# 27_BoardPowerSupply_1.net
KiCad netlist of a schematic drawn in Altium Designer
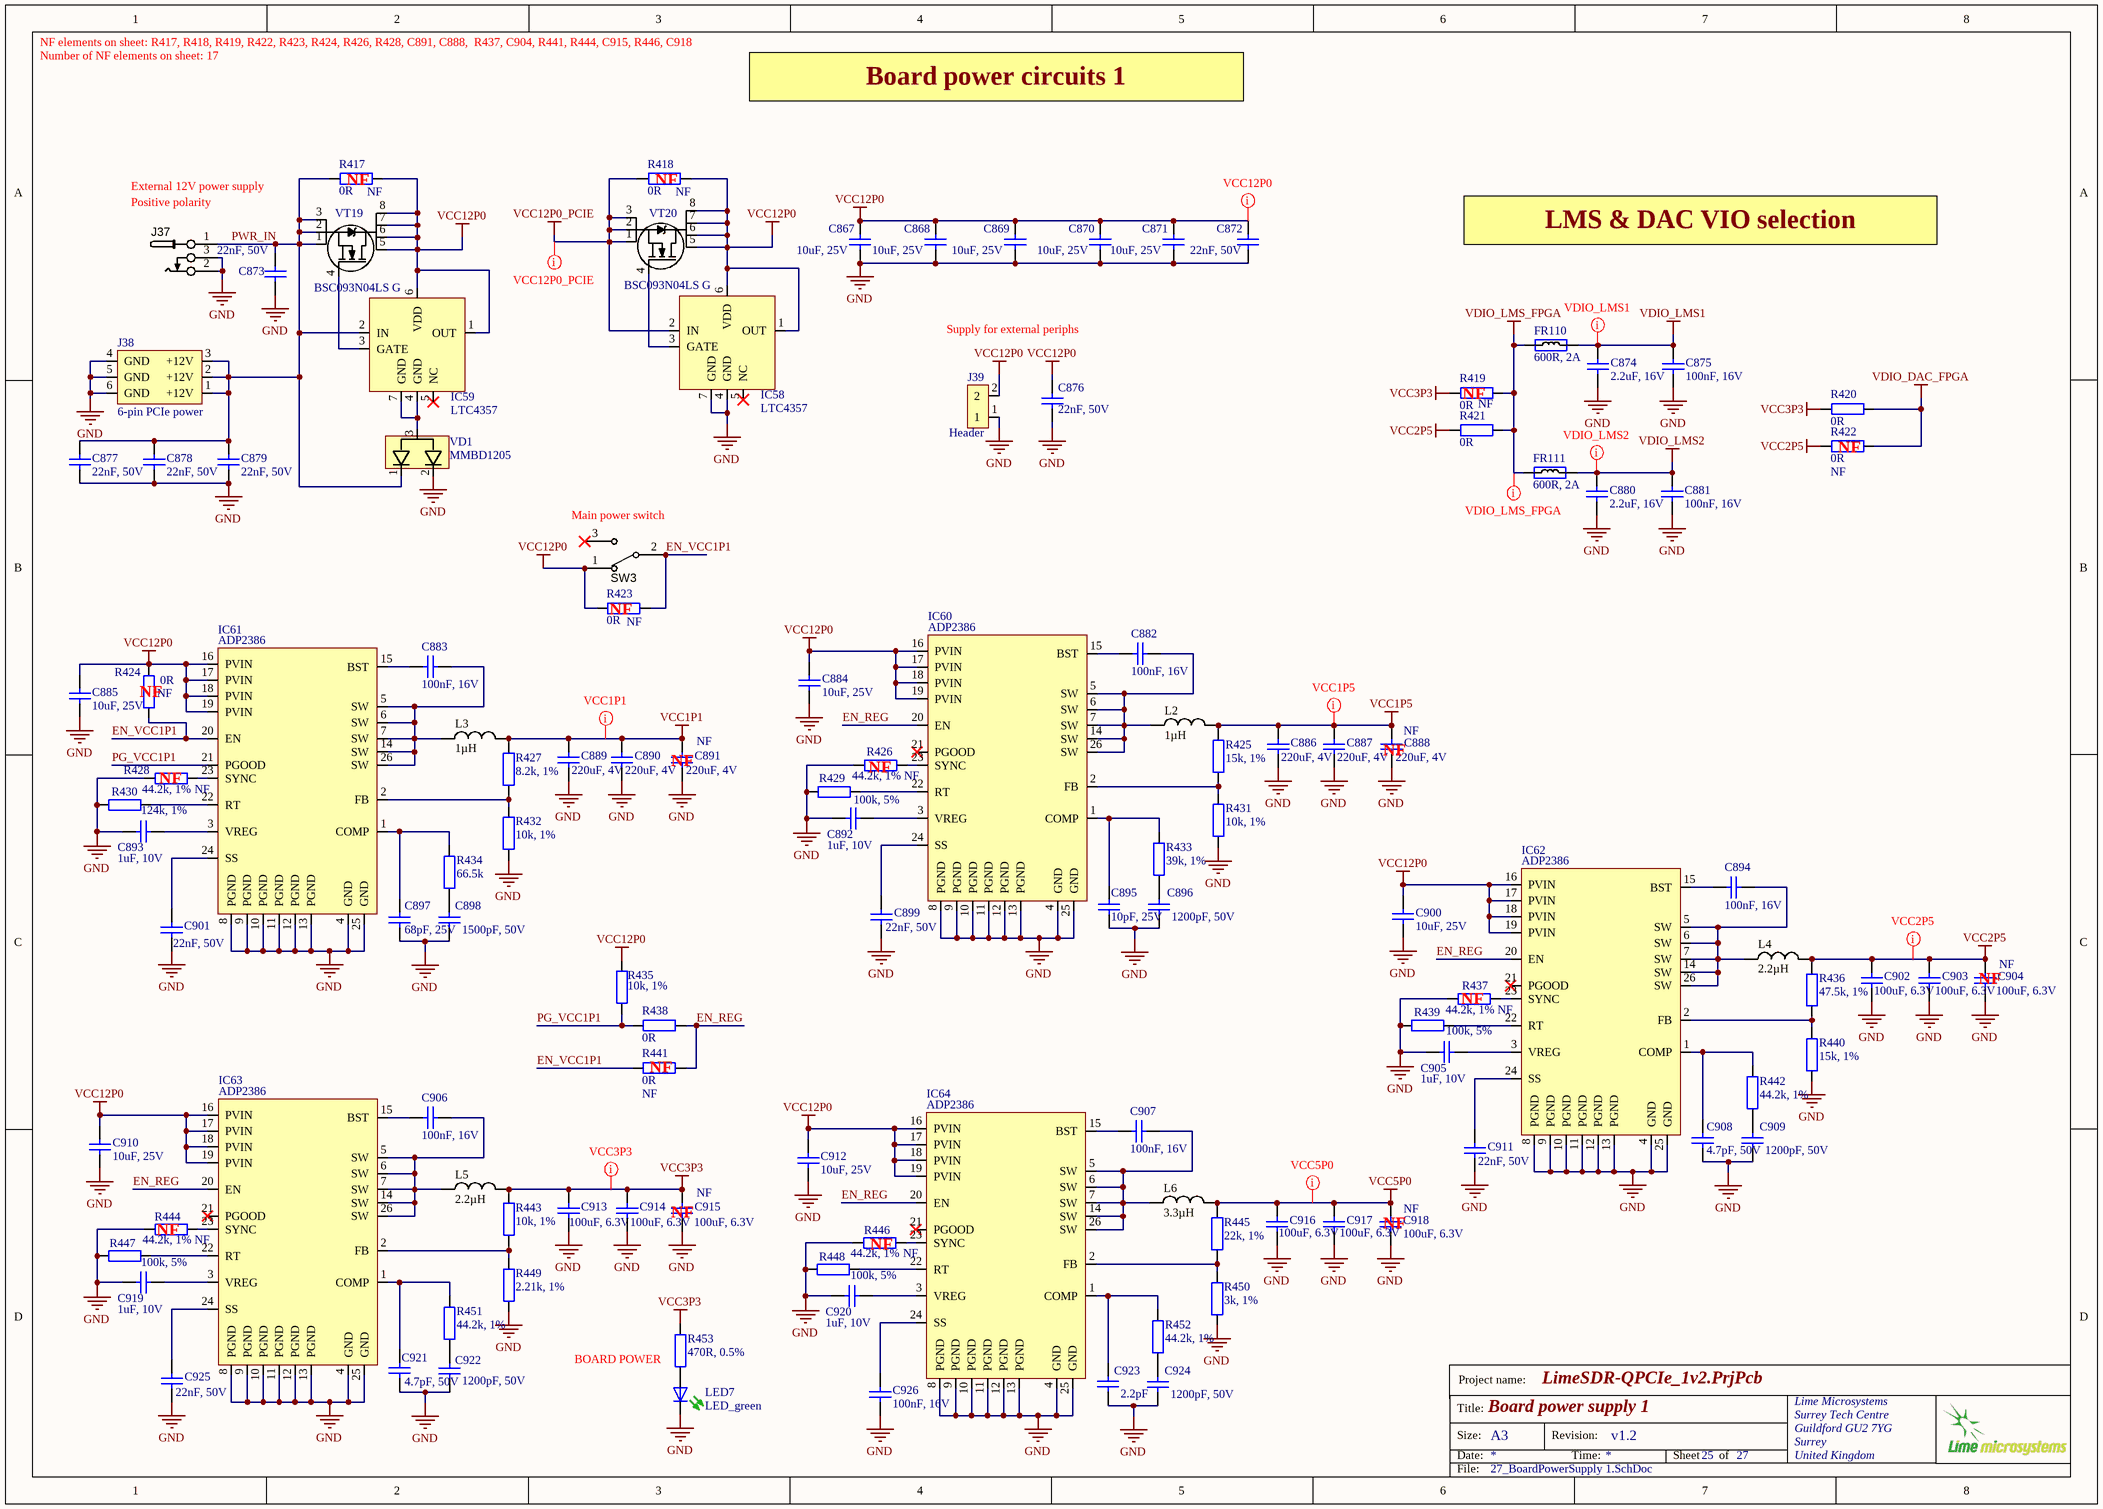
[diagram p0: 27_BoardPowerSupply 1.SchDoc]

(export (version "E")
  (design (tool "Eeschema 10.0.6"))
  (components
    (comp (ref "C867")
      (value "10uF, 25V")
      (footprint "CAP0603")
      (fields
        (field (name "MANUFACTURER") "Murata Electronics North America")
        (field (name "TOLERANCE") "±20%")
      )
      (libsource (lib "LimeMicroAltiumLib_schLib") (part "Cap_0603"))
    )
    (comp (ref "C868")
      (value "10uF, 25V")
      (footprint "CAP0603")
      (fields
        (field (name "MANUFACTURER") "Murata Electronics North America")
        (field (name "TOLERANCE") "±20%")
      )
      (libsource (lib "LimeMicroAltiumLib_schLib") (part "Cap_0603"))
    )
    (comp (ref "C869")
      (value "10uF, 25V")
      (footprint "CAP0603")
      (fields
        (field (name "MANUFACTURER") "Murata Electronics North America")
        (field (name "TOLERANCE") "±20%")
      )
      (libsource (lib "LimeMicroAltiumLib_schLib") (part "Cap_0603"))
    )
    (comp (ref "C870")
      (value "10uF, 25V")
      (footprint "CAP0603")
      (fields
        (field (name "MANUFACTURER") "Murata Electronics North America")
        (field (name "TOLERANCE") "±20%")
      )
      (libsource (lib "LimeMicroAltiumLib_schLib") (part "Cap_0603"))
    )
    (comp (ref "C871")
      (value "10uF, 25V")
      (footprint "CAP0603")
      (fields
        (field (name "MANUFACTURER") "Murata Electronics North America")
        (field (name "TOLERANCE") "±20%")
      )
      (libsource (lib "LimeMicroAltiumLib_schLib") (part "Cap_0603"))
    )
    (comp (ref "C872")
      (value "22nF, 50V")
      (footprint "CAP0402")
      (fields (field (name "TOLERANCE") "±10%") (field (name "MANUFACTURER") "Kemet"))
      (libsource (lib "LimeMicroAltiumLib_schLib") (part "Cap_0402"))
    )
    (comp (ref "C873")
      (value "22nF, 50V")
      (footprint "CAP0402")
      (fields (field (name "TOLERANCE") "±10%") (field (name "MANUFACTURER") "Kemet"))
      (libsource (lib "LimeMicroAltiumLib_schLib") (part "Cap_0402"))
    )
    (comp (ref "C874")
      (value "2.2uF, 16V")
      (footprint "CAP0402")
      (description "CAP CER 2.2UF 16V 10% X5R 0402")
      (fields (field (name "MANUFACTURER") "TDK Corporation") (field (name "TOLERANCE") "±20%"))
      (libsource (lib "LimeMicroAltiumLib_schLib") (part "Cap_0402"))
    )
    (comp (ref "C875")
      (value "100nF, 16V")
      (footprint "CAP0402")
      (fields
        (field (name "MANUFACTURER") "Murata Electronics")
        (field (name "TOLERANCE") "10 %")
        (field (name "MANUFACTURER PART NUMBER") "GRM155R71C104KA88D")
      )
      (libsource (lib "LimeMicroAltiumLib_schLib") (part "Cap_0402"))
    )
    (comp (ref "C876")
      (value "22nF, 50V")
      (footprint "CAP0402")
      (fields (field (name "TOLERANCE") "±10%") (field (name "MANUFACTURER") "Kemet"))
      (libsource (lib "LimeMicroAltiumLib_schLib") (part "Cap_0402"))
    )
    (comp (ref "C877")
      (value "22nF, 50V")
      (footprint "CAP0402")
      (fields (field (name "TOLERANCE") "±10%") (field (name "MANUFACTURER") "Kemet"))
      (libsource (lib "LimeMicroAltiumLib_schLib") (part "Cap_0402"))
    )
    (comp (ref "C878")
      (value "22nF, 50V")
      (footprint "CAP0402")
      (fields (field (name "TOLERANCE") "±10%") (field (name "MANUFACTURER") "Kemet"))
      (libsource (lib "LimeMicroAltiumLib_schLib") (part "Cap_0402"))
    )
    (comp (ref "C879")
      (value "22nF, 50V")
      (footprint "CAP0402")
      (fields (field (name "TOLERANCE") "±10%") (field (name "MANUFACTURER") "Kemet"))
      (libsource (lib "LimeMicroAltiumLib_schLib") (part "Cap_0402"))
    )
    (comp (ref "C880")
      (value "2.2uF, 16V")
      (footprint "CAP0402")
      (description "CAP CER 2.2UF 16V 10% X5R 0402")
      (fields (field (name "MANUFACTURER") "TDK Corporation") (field (name "TOLERANCE") "±20%"))
      (libsource (lib "LimeMicroAltiumLib_schLib") (part "Cap_0402"))
    )
    (comp (ref "C881")
      (value "100nF, 16V")
      (footprint "CAP0402")
      (fields
        (field (name "MANUFACTURER") "Murata Electronics")
        (field (name "TOLERANCE") "10 %")
        (field (name "MANUFACTURER PART NUMBER") "GRM155R71C104KA88D")
      )
      (libsource (lib "LimeMicroAltiumLib_schLib") (part "Cap_0402"))
    )
    (comp (ref "C882")
      (value "100nF, 16V")
      (footprint "CAP0402")
      (fields
        (field (name "MANUFACTURER") "Murata Electronics")
        (field (name "TOLERANCE") "10 %")
        (field (name "MANUFACTURER PART NUMBER") "GRM155R71C104KA88D")
      )
      (libsource (lib "LimeMicroAltiumLib_schLib") (part "Cap_0402"))
    )
    (comp (ref "C883")
      (value "100nF, 16V")
      (footprint "CAP0402")
      (fields
        (field (name "MANUFACTURER") "Murata Electronics")
        (field (name "TOLERANCE") "10 %")
        (field (name "MANUFACTURER PART NUMBER") "GRM155R71C104KA88D")
      )
      (libsource (lib "LimeMicroAltiumLib_schLib") (part "Cap_0402"))
    )
    (comp (ref "C884")
      (value "10uF, 25V")
      (footprint "CAP0805")
      (fields
        (field (name "MANUFACTURER") "Murata Electronics North America")
        (field (name "TOLERANCE") "±10%")
      )
      (libsource (lib "LimeMicroAltiumLib_schLib") (part "Cap_0805"))
    )
    (comp (ref "C885")
      (value "10uF, 25V")
      (footprint "CAP0805")
      (fields
        (field (name "MANUFACTURER") "Murata Electronics North America")
        (field (name "TOLERANCE") "±10%")
      )
      (libsource (lib "LimeMicroAltiumLib_schLib") (part "Cap_0805"))
    )
    (comp (ref "C886")
      (value "220uF, 4V")
      (footprint "CAP1206")
      (fields
        (field (name "MANUFACTURER PART NUMBER") "GRM31CR60G227ME11L")
        (field (name "MANUFACTURER") "Murata Electronics North America")
        (field (name "TOLERANCE") "±20%")
      )
      (libsource (lib "LimeFPGAboard_schLib") (part "Cap_1206"))
    )
    (comp (ref "C887")
      (value "220uF, 4V")
      (footprint "CAP1206")
      (fields
        (field (name "MANUFACTURER PART NUMBER") "GRM31CR60G227ME11L")
        (field (name "MANUFACTURER") "Murata Electronics North America")
        (field (name "TOLERANCE") "±20%")
      )
      (libsource (lib "LimeFPGAboard_schLib") (part "Cap_1206"))
    )
    (comp (ref "C888")
      (value "220uF, 4V")
      (footprint "CAP1206")
      (fields
        (field (name "MANUFACTURER PART NUMBER") "GRM31CR60G227ME11L")
        (field (name "MANUFACTURER") "Murata Electronics North America")
        (field (name "TOLERANCE") "±20%")
        (field (name "ASSEMBLY INFO") "NF")
      )
      (libsource (lib "LimeFPGAboard_schLib") (part "Cap_1206"))
    )
    (comp (ref "C889")
      (value "220uF, 4V")
      (footprint "CAP1206")
      (fields
        (field (name "MANUFACTURER PART NUMBER") "GRM31CR60G227ME11L")
        (field (name "MANUFACTURER") "Murata Electronics North America")
        (field (name "TOLERANCE") "±20%")
      )
      (libsource (lib "LimeFPGAboard_schLib") (part "Cap_1206"))
    )
    (comp (ref "C890")
      (value "220uF, 4V")
      (footprint "CAP1206")
      (fields
        (field (name "MANUFACTURER PART NUMBER") "GRM31CR60G227ME11L")
        (field (name "MANUFACTURER") "Murata Electronics North America")
        (field (name "TOLERANCE") "±20%")
      )
      (libsource (lib "LimeFPGAboard_schLib") (part "Cap_1206"))
    )
    (comp (ref "C891")
      (value "220uF, 4V")
      (footprint "CAP1206")
      (fields
        (field (name "MANUFACTURER PART NUMBER") "GRM31CR60G227ME11L")
        (field (name "MANUFACTURER") "Murata Electronics North America")
        (field (name "TOLERANCE") "±20%")
        (field (name "ASSEMBLY INFO") "NF")
      )
      (libsource (lib "LimeFPGAboard_schLib") (part "Cap_1206"))
    )
    (comp (ref "C892")
      (value "1uF, 10V")
      (footprint "CAP0402")
      (fields (field (name "MANUFACTURER") "TDK"))
      (libsource (lib "LimeMicroAltiumLib_schLib") (part "Cap_0402"))
    )
    (comp (ref "C893")
      (value "1uF, 10V")
      (footprint "CAP0402")
      (fields (field (name "MANUFACTURER") "TDK"))
      (libsource (lib "LimeMicroAltiumLib_schLib") (part "Cap_0402"))
    )
    (comp (ref "C894")
      (value "100nF, 16V")
      (footprint "CAP0402")
      (fields
        (field (name "MANUFACTURER") "Murata Electronics")
        (field (name "TOLERANCE") "10 %")
        (field (name "MANUFACTURER PART NUMBER") "GRM155R71C104KA88D")
      )
      (libsource (lib "LimeMicroAltiumLib_schLib") (part "Cap_0402"))
    )
    (comp (ref "C895")
      (value "10pF, 25V")
      (footprint "CAP0402")
      (fields (field (name "MANUFACTURER") "AVX"))
      (libsource (lib "LimeMicroAltiumLib_schLib") (part "Cap_0402"))
    )
    (comp (ref "C896")
      (value "1200pF, 50V")
      (footprint "CAP0402")
      (fields (field (name "MANUFACTURER") "Kemet") (field (name "TOLERANCE") "±5%"))
      (libsource (lib "LimeMicroAltiumLib_schLib") (part "Cap_0402"))
    )
    (comp (ref "C897")
      (value "68pF, 25V")
      (footprint "CAP0402")
      (fields (field (name "TOLERANCE") "±1%") (field (name "MANUFACTURER") "Kemet"))
      (libsource (lib "LimeMicroAltiumLib_schLib") (part "Cap_0402"))
    )
    (comp (ref "C898")
      (value "1500pF, 50V")
      (footprint "CAP0402")
      (fields
        (field (name "MANUFACTURER") "Samsung Electro-Mechanics America, Inc.")
        (field (name "TOLERANCE") "±10%")
      )
      (libsource (lib "LimeMicroAltiumLib_schLib") (part "Cap_0402"))
    )
    (comp (ref "C899")
      (value "22nF, 50V")
      (footprint "CAP0402")
      (fields (field (name "TOLERANCE") "±10%") (field (name "MANUFACTURER") "Kemet"))
      (libsource (lib "LimeMicroAltiumLib_schLib") (part "Cap_0402"))
    )
    (comp (ref "C900")
      (value "10uF, 25V")
      (footprint "CAP0805")
      (fields
        (field (name "MANUFACTURER") "Murata Electronics North America")
        (field (name "TOLERANCE") "±10%")
      )
      (libsource (lib "LimeMicroAltiumLib_schLib") (part "Cap_0805"))
    )
    (comp (ref "C901")
      (value "22nF, 50V")
      (footprint "CAP0402")
      (fields (field (name "TOLERANCE") "±10%") (field (name "MANUFACTURER") "Kemet"))
      (libsource (lib "LimeMicroAltiumLib_schLib") (part "Cap_0402"))
    )
    (comp (ref "C902")
      (value "100uF, 6.3V")
      (footprint "CAP1206")
      (fields (field (name "MANUFACTURER") "MURATA"))
      (libsource (lib "LimeFPGAboard_schLib") (part "Cap_1206"))
    )
    (comp (ref "C903")
      (value "100uF, 6.3V")
      (footprint "CAP1206")
      (fields (field (name "MANUFACTURER") "MURATA"))
      (libsource (lib "LimeFPGAboard_schLib") (part "Cap_1206"))
    )
    (comp (ref "C904")
      (value "100uF, 6.3V")
      (footprint "CAP1206")
      (fields (field (name "MANUFACTURER") "MURATA") (field (name "ASSEMBLY INFO") "NF"))
      (libsource (lib "LimeFPGAboard_schLib") (part "Cap_1206"))
    )
    (comp (ref "C905")
      (value "1uF, 10V")
      (footprint "CAP0402")
      (fields (field (name "MANUFACTURER") "TDK"))
      (libsource (lib "LimeMicroAltiumLib_schLib") (part "Cap_0402"))
    )
    (comp (ref "C906")
      (value "100nF, 16V")
      (footprint "CAP0402")
      (fields
        (field (name "MANUFACTURER") "Murata Electronics")
        (field (name "TOLERANCE") "10 %")
        (field (name "MANUFACTURER PART NUMBER") "GRM155R71C104KA88D")
      )
      (libsource (lib "LimeMicroAltiumLib_schLib") (part "Cap_0402"))
    )
    (comp (ref "C907")
      (value "100nF, 16V")
      (footprint "CAP0402")
      (fields
        (field (name "MANUFACTURER") "Murata Electronics")
        (field (name "TOLERANCE") "10 %")
        (field (name "MANUFACTURER PART NUMBER") "GRM155R71C104KA88D")
      )
      (libsource (lib "LimeMicroAltiumLib_schLib") (part "Cap_0402"))
    )
    (comp (ref "C908")
      (value "4.7pF, 50V")
      (footprint "CAP0402")
      (fields (field (name "MANUFACTURER") "MURATA"))
      (libsource (lib "LimeMicroAltiumLib_schLib") (part "Cap_0402"))
    )
    (comp (ref "C909")
      (value "1200pF, 50V")
      (footprint "CAP0402")
      (fields (field (name "MANUFACTURER") "Kemet") (field (name "TOLERANCE") "±5%"))
      (libsource (lib "LimeMicroAltiumLib_schLib") (part "Cap_0402"))
    )
    (comp (ref "C910")
      (value "10uF, 25V")
      (footprint "CAP0805")
      (fields
        (field (name "MANUFACTURER") "Murata Electronics North America")
        (field (name "TOLERANCE") "±10%")
      )
      (libsource (lib "LimeMicroAltiumLib_schLib") (part "Cap_0805"))
    )
    (comp (ref "C911")
      (value "22nF, 50V")
      (footprint "CAP0402")
      (fields (field (name "TOLERANCE") "±10%") (field (name "MANUFACTURER") "Kemet"))
      (libsource (lib "LimeMicroAltiumLib_schLib") (part "Cap_0402"))
    )
    (comp (ref "C912")
      (value "10uF, 25V")
      (footprint "CAP0805")
      (fields
        (field (name "MANUFACTURER") "Murata Electronics North America")
        (field (name "TOLERANCE") "±10%")
      )
      (libsource (lib "LimeMicroAltiumLib_schLib") (part "Cap_0805"))
    )
    (comp (ref "C913")
      (value "100uF, 6.3V")
      (footprint "CAP1206")
      (fields (field (name "MANUFACTURER") "MURATA"))
      (libsource (lib "LimeFPGAboard_schLib") (part "Cap_1206"))
    )
    (comp (ref "C914")
      (value "100uF, 6.3V")
      (footprint "CAP1206")
      (fields (field (name "MANUFACTURER") "MURATA"))
      (libsource (lib "LimeFPGAboard_schLib") (part "Cap_1206"))
    )
    (comp (ref "C915")
      (value "100uF, 6.3V")
      (footprint "CAP1206")
      (fields (field (name "MANUFACTURER") "MURATA") (field (name "ASSEMBLY INFO") "NF"))
      (libsource (lib "LimeFPGAboard_schLib") (part "Cap_1206"))
    )
    (comp (ref "C916")
      (value "100uF, 6.3V")
      (footprint "CAP1206")
      (fields (field (name "MANUFACTURER") "MURATA"))
      (libsource (lib "LimeFPGAboard_schLib") (part "Cap_1206"))
    )
    (comp (ref "C917")
      (value "100uF, 6.3V")
      (footprint "CAP1206")
      (fields (field (name "MANUFACTURER") "MURATA"))
      (libsource (lib "LimeFPGAboard_schLib") (part "Cap_1206"))
    )
    (comp (ref "C918")
      (value "100uF, 6.3V")
      (footprint "CAP1206")
      (fields (field (name "MANUFACTURER") "MURATA") (field (name "ASSEMBLY INFO") "NF"))
      (libsource (lib "LimeFPGAboard_schLib") (part "Cap_1206"))
    )
    (comp (ref "C919")
      (value "1uF, 10V")
      (footprint "CAP0402")
      (fields (field (name "MANUFACTURER") "TDK"))
      (libsource (lib "LimeMicroAltiumLib_schLib") (part "Cap_0402"))
    )
    (comp (ref "C920")
      (value "1uF, 10V")
      (footprint "CAP0402")
      (fields (field (name "MANUFACTURER") "TDK"))
      (libsource (lib "LimeMicroAltiumLib_schLib") (part "Cap_0402"))
    )
    (comp (ref "C921")
      (value "4.7pF, 50V")
      (footprint "CAP0402")
      (fields (field (name "MANUFACTURER") "MURATA"))
      (libsource (lib "LimeMicroAltiumLib_schLib") (part "Cap_0402"))
    )
    (comp (ref "C922")
      (value "1200pF, 50V")
      (footprint "CAP0402")
      (fields (field (name "MANUFACTURER") "Kemet") (field (name "TOLERANCE") "±5%"))
      (libsource (lib "LimeMicroAltiumLib_schLib") (part "Cap_0402"))
    )
    (comp (ref "C923")
      (value "2.2pF")
      (footprint "CAP0402")
      (fields
        (field (name "TOLERANCE") "±0.25pF")
        (field (name "MANUFACTURER") "Samsung Electro-Mechanics America, Inc.")
      )
      (libsource (lib "LimeMicroAltiumLib_schLib") (part "Cap_0402"))
    )
    (comp (ref "C924")
      (value "1200pF, 50V")
      (footprint "CAP0402")
      (fields (field (name "MANUFACTURER") "Kemet") (field (name "TOLERANCE") "±5%"))
      (libsource (lib "LimeMicroAltiumLib_schLib") (part "Cap_0402"))
    )
    (comp (ref "C925")
      (value "22nF, 50V")
      (footprint "CAP0402")
      (fields (field (name "TOLERANCE") "±10%") (field (name "MANUFACTURER") "Kemet"))
      (libsource (lib "LimeMicroAltiumLib_schLib") (part "Cap_0402"))
    )
    (comp (ref "C926")
      (value "100nF, 16V")
      (footprint "CAP0402")
      (fields
        (field (name "MANUFACTURER") "Murata Electronics")
        (field (name "TOLERANCE") "10 %")
        (field (name "MANUFACTURER PART NUMBER") "GRM155R71C104KA88D")
      )
      (libsource (lib "LimeMicroAltiumLib_schLib") (part "Cap_0402"))
    )
    (comp (ref "FR110")
      (value "600R, 2A")
      (footprint "RES0805")
      (fields (field (name "MANUFACTURER") "TDK"))
      (libsource (lib "LimeMicroAltiumLib_schLib") (part "Ferrite"))
    )
    (comp (ref "FR111")
      (value "600R, 2A")
      (footprint "RES0805")
      (fields (field (name "MANUFACTURER") "TDK"))
      (libsource (lib "LimeMicroAltiumLib_schLib") (part "Ferrite"))
    )
    (comp (ref "IC58")
      (value "LTC4357")
      (footprint "LTC4357")
      (libsource (lib "LimeFPGAboard_schLib") (part "LTC4357"))
    )
    (comp (ref "IC59")
      (value "LTC4357")
      (footprint "LTC4357")
      (libsource (lib "LimeFPGAboard_schLib") (part "LTC4357"))
    )
    (comp (ref "IC60")
      (value "ADP2386")
      (footprint "ADP2386")
      (fields (field (name "MANUFACTURER") "Analog Devices Inc."))
      (libsource (lib "LimeMicroAltiumLib_schLib") (part "ADP2386"))
    )
    (comp (ref "IC61")
      (value "ADP2386")
      (footprint "ADP2386")
      (fields (field (name "MANUFACTURER") "Analog Devices Inc."))
      (libsource (lib "LimeMicroAltiumLib_schLib") (part "ADP2386"))
    )
    (comp (ref "IC62")
      (value "ADP2386")
      (footprint "ADP2386")
      (fields (field (name "MANUFACTURER") "Analog Devices Inc."))
      (libsource (lib "LimeMicroAltiumLib_schLib") (part "ADP2386"))
    )
    (comp (ref "IC63")
      (value "ADP2386")
      (footprint "ADP2386")
      (fields (field (name "MANUFACTURER") "Analog Devices Inc."))
      (libsource (lib "LimeMicroAltiumLib_schLib") (part "ADP2386"))
    )
    (comp (ref "IC64")
      (value "ADP2386")
      (footprint "ADP2386")
      (fields (field (name "MANUFACTURER") "Analog Devices Inc."))
      (libsource (lib "LimeMicroAltiumLib_schLib") (part "ADP2386"))
    )
    (comp (ref "J37")
      (value "CONN_PWR_JACK_2.1x5.5mm")
      (footprint "CONN_PWR_JACK_v2")
      (description "Power Connector, THT, 2.1mm ID, 5.5mm OD")
      (fields (field (name "MANUFACTURER") "SWITCHCRAFT"))
      (libsource (lib "LimeFPGAboard_schLib") (part "CONN_PWR_JACK_2.1x5.5mm"))
    )
    (comp (ref "J38")
      (value "6-pin PCIe power")
      (footprint "PCIe_POWER_HEADER_6PIN")
      (fields (field (name "MANUFACTURER") "Molex Connector Corporation"))
      (libsource (lib "LimeMicroAltiumLib_schLib") (part "PCIe_PWR_HEADER_6PIN"))
    )
    (comp (ref "J39")
      (value "Header")
      (footprint "HDR_1x2")
      (fields (field (name "MANUFACTURER") "3M"))
      (libsource (lib "LimeFPGAboard_schLib") (part "Jumper"))
    )
    (comp (ref "L2")
      (value "1µH")
      (footprint "FDVE1040_TOKO_INDUCTOR")
      (fields (field (name "TOLERANCE") "±20%") (field (name "MANUFACTURER") "Vishay Dale"))
      (libsource (lib "LimeMicroAltiumLib_schLib") (part "Inductor_0603"))
    )
    (comp (ref "L3")
      (value "1µH")
      (footprint "FDVE1040_TOKO_INDUCTOR")
      (fields (field (name "TOLERANCE") "±20%") (field (name "MANUFACTURER") "Vishay Dale"))
      (libsource (lib "LimeMicroAltiumLib_schLib") (part "Inductor_0603"))
    )
    (comp (ref "L4")
      (value "2.2µH")
      (footprint "FDVE1040_TOKO_INDUCTOR")
      (fields (field (name "TOLERANCE") "±20%") (field (name "MANUFACTURER") "Vishay Dale"))
      (libsource (lib "LimeMicroAltiumLib_schLib") (part "Inductor_0603"))
    )
    (comp (ref "L5")
      (value "2.2µH")
      (footprint "FDVE1040_TOKO_INDUCTOR")
      (fields (field (name "TOLERANCE") "±20%") (field (name "MANUFACTURER") "Vishay Dale"))
      (libsource (lib "LimeMicroAltiumLib_schLib") (part "Inductor_0603"))
    )
    (comp (ref "L6")
      (value "3.3µH")
      (footprint "FDVE1040_TOKO_INDUCTOR")
      (fields
        (field (name "MANUFACTURER") "Vishay Dale")
        (field (name "TOLERANCE") "±20%")
        (field (name "MANUFACTURER PART NUMBER") "IHLP4040DZER3R3M01")
      )
      (libsource (lib "LimeMicroAltiumLib_schLib") (part "Inductor_0603"))
    )
    (comp (ref "LED7")
      (value "LED_green")
      (footprint "LED-0603-GREEN")
      (fields
        (field (name "MANUFACTURER") "Avago Technologies US Inc.")
        (field (name "MANUFACTURER_1") "Broadcom Limited")
      )
      (libsource (lib "LimeMicroAltiumLib_schLib") (part "LED_green"))
    )
    (comp (ref "R417")
      (value "0R")
      (footprint "RES0805")
      (fields
        (field (name "ASSEMBLY INFO") "NF")
        (field (name "MANUFACTURER") "Vishay Dale")
        (field (name "TOLERANCE") "Jumper")
      )
      (libsource (lib "LimeMicroAltiumLib_schLib") (part "Res_0402"))
    )
    (comp (ref "R418")
      (value "0R")
      (footprint "RES0805")
      (fields
        (field (name "ASSEMBLY INFO") "NF")
        (field (name "MANUFACTURER") "Vishay Dale")
        (field (name "TOLERANCE") "Jumper")
      )
      (libsource (lib "LimeMicroAltiumLib_schLib") (part "Res_0402"))
    )
    (comp (ref "R419")
      (value "0R")
      (footprint "RES0402")
      (fields
        (field (name "ASSEMBLY INFO") "NF")
        (field (name "MANUFACTURER") "Yageo")
        (field (name "TOLERANCE") "Jumper")
      )
      (libsource (lib "LimeMicroAltiumLib_schLib") (part "Res_0402"))
    )
    (comp (ref "R420")
      (value "0R")
      (footprint "RES0402")
      (fields (field (name "MANUFACTURER") "Yageo") (field (name "TOLERANCE") "Jumper"))
      (libsource (lib "LimeMicroAltiumLib_schLib") (part "Res_0402"))
    )
    (comp (ref "R421")
      (value "0R")
      (footprint "RES0402")
      (fields (field (name "MANUFACTURER") "Yageo") (field (name "TOLERANCE") "Jumper"))
      (libsource (lib "LimeMicroAltiumLib_schLib") (part "Res_0402"))
    )
    (comp (ref "R422")
      (value "0R")
      (footprint "RES0402")
      (fields
        (field (name "ASSEMBLY INFO") "NF")
        (field (name "MANUFACTURER") "Yageo")
        (field (name "TOLERANCE") "Jumper")
      )
      (libsource (lib "LimeMicroAltiumLib_schLib") (part "Res_0402"))
    )
    (comp (ref "R423")
      (value "0R")
      (footprint "RES0402")
      (fields
        (field (name "ASSEMBLY INFO") "NF")
        (field (name "MANUFACTURER") "Yageo")
        (field (name "TOLERANCE") "Jumper")
      )
      (libsource (lib "LimeMicroAltiumLib_schLib") (part "Res_0402"))
    )
    (comp (ref "R424")
      (value "0R")
      (footprint "RES0402")
      (fields (field (name "MANUFACTURER") "Yageo") (field (name "ASSEMBLY INFO") "NF"))
      (libsource (lib "LimeFPGAboard_schLib") (part "Res_0402"))
    )
    (comp (ref "R425")
      (value "15k, 1%")
      (footprint "RES0402")
      (fields (field (name "TOLERANCE") "±1%") (field (name "MANUFACTURER") "Yageo"))
      (libsource (lib "LimeMicroAltiumLib_schLib") (part "Res_0402"))
    )
    (comp (ref "R426")
      (value "44.2k, 1%")
      (footprint "RES0402")
      (fields
        (field (name "ASSEMBLY INFO") "NF")
        (field (name "TOLERANCE") "±1%")
        (field (name "MANUFACTURER") "Panasonic Electronic Components")
      )
      (libsource (lib "LimeMicroAltiumLib_schLib") (part "Res_0402"))
    )
    (comp (ref "R427")
      (value "8.2k, 1%")
      (footprint "RES0402")
      (fields (field (name "MANUFACTURER") "Yageo") (field (name "TOLERANCE") "±1%"))
      (libsource (lib "LimeMicroAltiumLib_schLib") (part "Res_0402"))
    )
    (comp (ref "R428")
      (value "44.2k, 1%")
      (footprint "RES0402")
      (fields
        (field (name "ASSEMBLY INFO") "NF")
        (field (name "TOLERANCE") "±1%")
        (field (name "MANUFACTURER") "Panasonic Electronic Components")
      )
      (libsource (lib "LimeMicroAltiumLib_schLib") (part "Res_0402"))
    )
    (comp (ref "R429")
      (value "100k, 5%")
      (footprint "RES0402")
      (fields
        (field (name "MANUFACTURER") "Panasonic Electronic Components")
        (field (name "TOLERANCE") "±5%")
      )
      (libsource (lib "LimeMicroAltiumLib_schLib") (part "Res_0402"))
    )
    (comp (ref "R430")
      (value "124k, 1%")
      (footprint "RES0402")
      (fields
        (field (name "MANUFACTURER") "Panasonic Electronic Components")
        (field (name "TOLERANCE") "±1%")
      )
      (libsource (lib "LimeMicroAltiumLib_schLib") (part "Res_0402"))
    )
    (comp (ref "R431")
      (value "10k, 1%")
      (footprint "RES0402")
      (fields (field (name "MANUFACTURER") "Yageo") (field (name "TOLERANCE") "±1%"))
      (libsource (lib "LimeMicroAltiumLib_schLib") (part "Res_0402"))
    )
    (comp (ref "R432")
      (value "10k, 1%")
      (footprint "RES0402")
      (fields (field (name "MANUFACTURER") "Yageo") (field (name "TOLERANCE") "±1%"))
      (libsource (lib "LimeMicroAltiumLib_schLib") (part "Res_0402"))
    )
    (comp (ref "R433")
      (value "39k, 1%")
      (footprint "RES0402")
      (fields (field (name "TOLERANCE") "±1%") (field (name "MANUFACTURER") "Vishay Dale"))
      (libsource (lib "LimeMicroAltiumLib_schLib") (part "Res_0402"))
    )
    (comp (ref "R434")
      (value "66.5k")
      (footprint "RES0402")
      (fields
        (field (name "MANUFACTURER") "Panasonic Electronic Components")
        (field (name "TOLERANCE") "±1%")
      )
      (libsource (lib "LimeMicroAltiumLib_schLib") (part "Res_0402"))
    )
    (comp (ref "R435")
      (value "10k, 1%")
      (footprint "RES0402")
      (fields (field (name "MANUFACTURER") "Yageo") (field (name "TOLERANCE") "±1%"))
      (libsource (lib "LimeMicroAltiumLib_schLib") (part "Res_0402"))
    )
    (comp (ref "R436")
      (value "47.5k, 1%")
      (footprint "RES0402")
      (fields
        (field (name "MANUFACTURER PART NUMBER") "ERJ-2RKF4752X")
        (field (name "MANUFACTURER") "Panasonic Electronic Components")
        (field (name "TOLERANCE") "±1%")
      )
      (libsource (lib "LimeMicroAltiumLib_schLib") (part "Res_0402"))
    )
    (comp (ref "R437")
      (value "44.2k, 1%")
      (footprint "RES0402")
      (fields
        (field (name "ASSEMBLY INFO") "NF")
        (field (name "TOLERANCE") "±1%")
        (field (name "MANUFACTURER") "Panasonic Electronic Components")
      )
      (libsource (lib "LimeMicroAltiumLib_schLib") (part "Res_0402"))
    )
    (comp (ref "R438")
      (value "0R")
      (footprint "RES0402")
      (fields (field (name "MANUFACTURER") "Yageo") (field (name "TOLERANCE") "Jumper"))
      (libsource (lib "LimeMicroAltiumLib_schLib") (part "Res_0402"))
    )
    (comp (ref "R439")
      (value "100k, 5%")
      (footprint "RES0402")
      (fields
        (field (name "MANUFACTURER") "Panasonic Electronic Components")
        (field (name "TOLERANCE") "±5%")
      )
      (libsource (lib "LimeMicroAltiumLib_schLib") (part "Res_0402"))
    )
    (comp (ref "R440")
      (value "15k, 1%")
      (footprint "RES0402")
      (fields (field (name "TOLERANCE") "±1%") (field (name "MANUFACTURER") "Yageo"))
      (libsource (lib "LimeMicroAltiumLib_schLib") (part "Res_0402"))
    )
    (comp (ref "R441")
      (value "0R")
      (footprint "RES0402")
      (fields
        (field (name "ASSEMBLY INFO") "NF")
        (field (name "MANUFACTURER") "Yageo")
        (field (name "TOLERANCE") "Jumper")
      )
      (libsource (lib "LimeMicroAltiumLib_schLib") (part "Res_0402"))
    )
    (comp (ref "R442")
      (value "44.2k, 1%")
      (footprint "RES0402")
      (fields
        (field (name "TOLERANCE") "±1%")
        (field (name "MANUFACTURER") "Panasonic Electronic Components")
      )
      (libsource (lib "LimeMicroAltiumLib_schLib") (part "Res_0402"))
    )
    (comp (ref "R443")
      (value "10k, 1%")
      (footprint "RES0402")
      (fields (field (name "MANUFACTURER") "Yageo") (field (name "TOLERANCE") "±1%"))
      (libsource (lib "LimeMicroAltiumLib_schLib") (part "Res_0402"))
    )
    (comp (ref "R444")
      (value "44.2k, 1%")
      (footprint "RES0402")
      (fields
        (field (name "ASSEMBLY INFO") "NF")
        (field (name "TOLERANCE") "±1%")
        (field (name "MANUFACTURER") "Panasonic Electronic Components")
      )
      (libsource (lib "LimeMicroAltiumLib_schLib") (part "Res_0402"))
    )
    (comp (ref "R445")
      (value "22k, 1%")
      (footprint "RES0402")
      (fields (field (name "MANUFACTURER") "Yageo") (field (name "TOLERANCE") "±1%"))
      (libsource (lib "LimeMicroAltiumLib_schLib") (part "Res_0402"))
    )
    (comp (ref "R446")
      (value "44.2k, 1%")
      (footprint "RES0402")
      (fields
        (field (name "ASSEMBLY INFO") "NF")
        (field (name "TOLERANCE") "±1%")
        (field (name "MANUFACTURER") "Panasonic Electronic Components")
      )
      (libsource (lib "LimeMicroAltiumLib_schLib") (part "Res_0402"))
    )
    (comp (ref "R447")
      (value "100k, 5%")
      (footprint "RES0402")
      (fields
        (field (name "MANUFACTURER") "Panasonic Electronic Components")
        (field (name "TOLERANCE") "±5%")
      )
      (libsource (lib "LimeMicroAltiumLib_schLib") (part "Res_0402"))
    )
    (comp (ref "R448")
      (value "100k, 5%")
      (footprint "RES0402")
      (fields
        (field (name "MANUFACTURER") "Panasonic Electronic Components")
        (field (name "TOLERANCE") "±5%")
      )
      (libsource (lib "LimeMicroAltiumLib_schLib") (part "Res_0402"))
    )
    (comp (ref "R449")
      (value "2.21k, 1%")
      (footprint "RES0402")
      (fields (field (name "MANUFACTURER") "Stackpole Electronics Inc.") (field (name "TOLERANCE") "±1%"))
      (libsource (lib "LimeMicroAltiumLib_schLib") (part "Res_0402"))
    )
    (comp (ref "R450")
      (value "3k, 1%")
      (footprint "RES0402")
      (fields (field (name "TOLERANCE") "±1%") (field (name "MANUFACTURER") "Vishay Dale"))
      (libsource (lib "LimeMicroAltiumLib_schLib") (part "Res_0402"))
    )
    (comp (ref "R451")
      (value "44.2k, 1%")
      (footprint "RES0402")
      (fields
        (field (name "TOLERANCE") "±1%")
        (field (name "MANUFACTURER") "Panasonic Electronic Components")
      )
      (libsource (lib "LimeMicroAltiumLib_schLib") (part "Res_0402"))
    )
    (comp (ref "R452")
      (value "44.2k, 1%")
      (footprint "RES0402")
      (fields
        (field (name "TOLERANCE") "±1%")
        (field (name "MANUFACTURER") "Panasonic Electronic Components")
      )
      (libsource (lib "LimeMicroAltiumLib_schLib") (part "Res_0402"))
    )
    (comp (ref "R453")
      (value "470R, 0.5%")
      (footprint "RES0402")
      (fields
        (field (name "TOLERANCE") "±0.5%")
        (field (name "MANUFACTURER") "Panasonic Electronic Components")
      )
      (libsource (lib "LimeMicroAltiumLib_schLib") (part "Res_0402"))
    )
    (comp (ref "SW3")
      (value "ON-ON")
      (footprint "SWITCH_SPDT_SLIDER_v2")
      (description "Switch THD vertical toggle SPDT")
      (fields (field (name "MANUFACTURER") "C&K Components"))
      (libsource (lib "LimeMicroAltiumLib_schLib") (part "SW_THD_SPDT_On-On_v2"))
    )
    (comp (ref "VD1")
      (value "MMBD1205")
      (footprint "SOT23-3_v2")
      (fields (field (name "MANUFACTURER") "Fairchild Semiconductor"))
      (libsource (lib "LimeFPGAboard_schLib") (part "MMBD1205"))
    )
    (comp (ref "VT19")
      (value "BSC093N04LS G")
      (footprint "BSC093N04LS_G")
      (fields (field (name "MANUFACTURER") "Infineon Technologies"))
      (libsource (lib "LimeFPGAboard_schLib") (part "BSC093N04LS_G"))
    )
    (comp (ref "VT20")
      (value "BSC093N04LS G")
      (footprint "BSC093N04LS_G")
      (fields (field (name "MANUFACTURER") "Infineon Technologies"))
      (libsource (lib "LimeFPGAboard_schLib") (part "BSC093N04LS_G"))
    )
  )
  (nets
    (net (code "1") (name "/EN_REG") (class "Default")
      (node (ref "IC60") (pin "20") (pinfunction "EN_20") (pintype "passive"))
      (node (ref "IC62") (pin "20") (pinfunction "EN_20") (pintype "passive"))
      (node (ref "IC63") (pin "20") (pinfunction "EN_20") (pintype "passive"))
      (node (ref "IC64") (pin "20") (pinfunction "EN_20") (pintype "passive"))
      (node (ref "R438") (pin "2") (pinfunction "2_2") (pintype "passive"))
      (node (ref "R441") (pin "2") (pinfunction "2_2") (pintype "passive"))
    )
    (net (code "2") (name "/EN_VCC1P1") (class "Default")
      (node (ref "IC61") (pin "20") (pinfunction "EN_20") (pintype "passive"))
      (node (ref "R423") (pin "2") (pinfunction "2_2") (pintype "passive"))
      (node (ref "R424") (pin "1") (pinfunction "1_1") (pintype "passive"))
      (node (ref "R441") (pin "1") (pinfunction "1_1") (pintype "passive"))
      (node (ref "SW3") (pin "2") (pinfunction "2_2") (pintype "passive"))
    )
    (net (code "3") (name "/PG_VCC1P1") (class "Default")
      (node (ref "IC61") (pin "21") (pinfunction "PGOOD_21") (pintype "passive"))
      (node (ref "R435") (pin "2") (pinfunction "2_2") (pintype "passive"))
      (node (ref "R438") (pin "1") (pinfunction "1_1") (pintype "passive"))
    )
    (net (code "4") (name "/PWR_IN") (class "Default")
      (node (ref "C873") (pin "1") (pinfunction "1_1") (pintype "passive"))
      (node (ref "C877") (pin "1") (pinfunction "1_1") (pintype "passive"))
      (node (ref "C878") (pin "1") (pinfunction "1_1") (pintype "passive"))
      (node (ref "C879") (pin "1") (pinfunction "1_1") (pintype "passive"))
      (node (ref "IC59") (pin "2") (pinfunction "IN_2") (pintype "passive"))
      (node (ref "J37") (pin "1") (pinfunction "1_1") (pintype "passive"))
      (node (ref "J38") (pin "1") (pinfunction "+12V_1") (pintype "passive"))
      (node (ref "J38") (pin "2") (pinfunction "+12V_2") (pintype "passive"))
      (node (ref "J38") (pin "3") (pinfunction "+12V_3") (pintype "passive"))
      (node (ref "R417") (pin "2") (pinfunction "2_2") (pintype "passive"))
      (node (ref "VD1") (pin "1") (pinfunction "1_1") (pintype "passive"))
      (node (ref "VT19") (pin "1") (pinfunction "S_1") (pintype "passive"))
      (node (ref "VT19") (pin "2") (pinfunction "S_2") (pintype "passive"))
      (node (ref "VT19") (pin "3") (pinfunction "S_3") (pintype "passive"))
    )
    (net (code "5") (name "GND") (class "Default")
      (node (ref "C867") (pin "1") (pinfunction "1_1") (pintype "passive"))
      (node (ref "C868") (pin "1") (pinfunction "1_1") (pintype "passive"))
      (node (ref "C869") (pin "1") (pinfunction "1_1") (pintype "passive"))
      (node (ref "C870") (pin "1") (pinfunction "1_1") (pintype "passive"))
      (node (ref "C871") (pin "1") (pinfunction "1_1") (pintype "passive"))
      (node (ref "C872") (pin "2") (pinfunction "2_2") (pintype "passive"))
      (node (ref "C873") (pin "2") (pinfunction "2_2") (pintype "passive"))
      (node (ref "C874") (pin "1") (pinfunction "1_1") (pintype "passive"))
      (node (ref "C875") (pin "2") (pinfunction "2_2") (pintype "passive"))
      (node (ref "C876") (pin "2") (pinfunction "2_2") (pintype "passive"))
      (node (ref "C877") (pin "2") (pinfunction "2_2") (pintype "passive"))
      (node (ref "C878") (pin "2") (pinfunction "2_2") (pintype "passive"))
      (node (ref "C879") (pin "2") (pinfunction "2_2") (pintype "passive"))
      (node (ref "C880") (pin "1") (pinfunction "1_1") (pintype "passive"))
      (node (ref "C881") (pin "2") (pinfunction "2_2") (pintype "passive"))
      (node (ref "C884") (pin "1") (pinfunction "1_1") (pintype "passive"))
      (node (ref "C885") (pin "1") (pinfunction "1_1") (pintype "passive"))
      (node (ref "C886") (pin "1") (pinfunction "1_1") (pintype "passive"))
      (node (ref "C887") (pin "1") (pinfunction "1_1") (pintype "passive"))
      (node (ref "C888") (pin "1") (pinfunction "1_1") (pintype "passive"))
      (node (ref "C889") (pin "1") (pinfunction "1_1") (pintype "passive"))
      (node (ref "C890") (pin "1") (pinfunction "1_1") (pintype "passive"))
      (node (ref "C891") (pin "1") (pinfunction "1_1") (pintype "passive"))
      (node (ref "C892") (pin "2") (pinfunction "2_2") (pintype "passive"))
      (node (ref "C893") (pin "2") (pinfunction "2_2") (pintype "passive"))
      (node (ref "C895") (pin "2") (pinfunction "2_2") (pintype "passive"))
      (node (ref "C896") (pin "2") (pinfunction "2_2") (pintype "passive"))
      (node (ref "C897") (pin "2") (pinfunction "2_2") (pintype "passive"))
      (node (ref "C898") (pin "2") (pinfunction "2_2") (pintype "passive"))
      (node (ref "C899") (pin "2") (pinfunction "2_2") (pintype "passive"))
      (node (ref "C900") (pin "1") (pinfunction "1_1") (pintype "passive"))
      (node (ref "C901") (pin "2") (pinfunction "2_2") (pintype "passive"))
      (node (ref "C902") (pin "1") (pinfunction "1_1") (pintype "passive"))
      (node (ref "C903") (pin "1") (pinfunction "1_1") (pintype "passive"))
      (node (ref "C904") (pin "1") (pinfunction "1_1") (pintype "passive"))
      (node (ref "C905") (pin "2") (pinfunction "2_2") (pintype "passive"))
      (node (ref "C908") (pin "2") (pinfunction "2_2") (pintype "passive"))
      (node (ref "C909") (pin "2") (pinfunction "2_2") (pintype "passive"))
      (node (ref "C910") (pin "1") (pinfunction "1_1") (pintype "passive"))
      (node (ref "C911") (pin "2") (pinfunction "2_2") (pintype "passive"))
      (node (ref "C912") (pin "1") (pinfunction "1_1") (pintype "passive"))
      (node (ref "C913") (pin "1") (pinfunction "1_1") (pintype "passive"))
      (node (ref "C914") (pin "1") (pinfunction "1_1") (pintype "passive"))
      (node (ref "C915") (pin "1") (pinfunction "1_1") (pintype "passive"))
      (node (ref "C916") (pin "1") (pinfunction "1_1") (pintype "passive"))
      (node (ref "C917") (pin "1") (pinfunction "1_1") (pintype "passive"))
      (node (ref "C918") (pin "1") (pinfunction "1_1") (pintype "passive"))
      (node (ref "C919") (pin "2") (pinfunction "2_2") (pintype "passive"))
      (node (ref "C920") (pin "2") (pinfunction "2_2") (pintype "passive"))
      (node (ref "C921") (pin "2") (pinfunction "2_2") (pintype "passive"))
      (node (ref "C922") (pin "2") (pinfunction "2_2") (pintype "passive"))
      (node (ref "C923") (pin "2") (pinfunction "2_2") (pintype "passive"))
      (node (ref "C924") (pin "2") (pinfunction "2_2") (pintype "passive"))
      (node (ref "C925") (pin "2") (pinfunction "2_2") (pintype "passive"))
      (node (ref "C926") (pin "1") (pinfunction "1_1") (pintype "passive"))
      (node (ref "IC58") (pin "4") (pinfunction "GND_4") (pintype "passive"))
      (node (ref "IC58") (pin "7") (pinfunction "GND_7") (pintype "passive"))
      (node (ref "IC60") (pin "10") (pinfunction "PGND_10") (pintype "passive"))
      (node (ref "IC60") (pin "11") (pinfunction "PGND_11") (pintype "passive"))
      (node (ref "IC60") (pin "12") (pinfunction "PGND_12") (pintype "passive"))
      (node (ref "IC60") (pin "13") (pinfunction "PGND_13") (pintype "passive"))
      (node (ref "IC60") (pin "25") (pinfunction "GND_25") (pintype "passive"))
      (node (ref "IC60") (pin "4") (pinfunction "GND_4") (pintype "passive"))
      (node (ref "IC60") (pin "8") (pinfunction "PGND_8") (pintype "passive"))
      (node (ref "IC60") (pin "9") (pinfunction "PGND_9") (pintype "passive"))
      (node (ref "IC61") (pin "10") (pinfunction "PGND_10") (pintype "passive"))
      (node (ref "IC61") (pin "11") (pinfunction "PGND_11") (pintype "passive"))
      (node (ref "IC61") (pin "12") (pinfunction "PGND_12") (pintype "passive"))
      (node (ref "IC61") (pin "13") (pinfunction "PGND_13") (pintype "passive"))
      (node (ref "IC61") (pin "25") (pinfunction "GND_25") (pintype "passive"))
      (node (ref "IC61") (pin "4") (pinfunction "GND_4") (pintype "passive"))
      (node (ref "IC61") (pin "8") (pinfunction "PGND_8") (pintype "passive"))
      (node (ref "IC61") (pin "9") (pinfunction "PGND_9") (pintype "passive"))
      (node (ref "IC62") (pin "10") (pinfunction "PGND_10") (pintype "passive"))
      (node (ref "IC62") (pin "11") (pinfunction "PGND_11") (pintype "passive"))
      (node (ref "IC62") (pin "12") (pinfunction "PGND_12") (pintype "passive"))
      (node (ref "IC62") (pin "13") (pinfunction "PGND_13") (pintype "passive"))
      (node (ref "IC62") (pin "25") (pinfunction "GND_25") (pintype "passive"))
      (node (ref "IC62") (pin "4") (pinfunction "GND_4") (pintype "passive"))
      (node (ref "IC62") (pin "8") (pinfunction "PGND_8") (pintype "passive"))
      (node (ref "IC62") (pin "9") (pinfunction "PGND_9") (pintype "passive"))
      (node (ref "IC63") (pin "10") (pinfunction "PGND_10") (pintype "passive"))
      (node (ref "IC63") (pin "11") (pinfunction "PGND_11") (pintype "passive"))
      (node (ref "IC63") (pin "12") (pinfunction "PGND_12") (pintype "passive"))
      (node (ref "IC63") (pin "13") (pinfunction "PGND_13") (pintype "passive"))
      (node (ref "IC63") (pin "25") (pinfunction "GND_25") (pintype "passive"))
      (node (ref "IC63") (pin "4") (pinfunction "GND_4") (pintype "passive"))
      (node (ref "IC63") (pin "8") (pinfunction "PGND_8") (pintype "passive"))
      (node (ref "IC63") (pin "9") (pinfunction "PGND_9") (pintype "passive"))
      (node (ref "IC64") (pin "10") (pinfunction "PGND_10") (pintype "passive"))
      (node (ref "IC64") (pin "11") (pinfunction "PGND_11") (pintype "passive"))
      (node (ref "IC64") (pin "12") (pinfunction "PGND_12") (pintype "passive"))
      (node (ref "IC64") (pin "13") (pinfunction "PGND_13") (pintype "passive"))
      (node (ref "IC64") (pin "25") (pinfunction "GND_25") (pintype "passive"))
      (node (ref "IC64") (pin "4") (pinfunction "GND_4") (pintype "passive"))
      (node (ref "IC64") (pin "8") (pinfunction "PGND_8") (pintype "passive"))
      (node (ref "IC64") (pin "9") (pinfunction "PGND_9") (pintype "passive"))
      (node (ref "J37") (pin "2") (pinfunction "2_2") (pintype "passive"))
      (node (ref "J37") (pin "3") (pinfunction "3_3") (pintype "passive"))
      (node (ref "J38") (pin "4") (pinfunction "GND_4") (pintype "passive"))
      (node (ref "J38") (pin "5") (pinfunction "GND_5") (pintype "passive"))
      (node (ref "J38") (pin "6") (pinfunction "GND_6") (pintype "passive"))
      (node (ref "J39") (pin "1") (pinfunction "1_1") (pintype "passive"))
      (node (ref "LED7") (pin "K") (pinfunction "C_K") (pintype "power_in"))
      (node (ref "R426") (pin "2") (pinfunction "2_2") (pintype "passive"))
      (node (ref "R428") (pin "2") (pinfunction "2_2") (pintype "passive"))
      (node (ref "R429") (pin "2") (pinfunction "2_2") (pintype "passive"))
      (node (ref "R430") (pin "2") (pinfunction "2_2") (pintype "passive"))
      (node (ref "R431") (pin "2") (pinfunction "2_2") (pintype "passive"))
      (node (ref "R432") (pin "2") (pinfunction "2_2") (pintype "passive"))
      (node (ref "R437") (pin "2") (pinfunction "2_2") (pintype "passive"))
      (node (ref "R439") (pin "2") (pinfunction "2_2") (pintype "passive"))
      (node (ref "R440") (pin "1") (pinfunction "1_1") (pintype "passive"))
      (node (ref "R444") (pin "2") (pinfunction "2_2") (pintype "passive"))
      (node (ref "R446") (pin "2") (pinfunction "2_2") (pintype "passive"))
      (node (ref "R447") (pin "2") (pinfunction "2_2") (pintype "passive"))
      (node (ref "R448") (pin "2") (pinfunction "2_2") (pintype "passive"))
      (node (ref "R449") (pin "1") (pinfunction "1_1") (pintype "passive"))
      (node (ref "R450") (pin "1") (pinfunction "1_1") (pintype "passive"))
      (node (ref "VD1") (pin "2") (pinfunction "2_2") (pintype "passive"))
    )
    (net (code "6") (name "Net-(C882-Pad2)") (class "Default")
      (node (ref "C882") (pin "2") (pinfunction "2_2") (pintype "passive"))
      (node (ref "IC60") (pin "14") (pinfunction "SW_14") (pintype "passive"))
      (node (ref "IC60") (pin "26") (pinfunction "SW_26") (pintype "passive"))
      (node (ref "IC60") (pin "5") (pinfunction "SW_5") (pintype "passive"))
      (node (ref "IC60") (pin "6") (pinfunction "SW_6") (pintype "passive"))
      (node (ref "IC60") (pin "7") (pinfunction "SW_7") (pintype "passive"))
      (node (ref "L2") (pin "1") (pinfunction "1_1") (pintype "passive"))
    )
    (net (code "7") (name "Net-(C883-Pad2)") (class "Default")
      (node (ref "C883") (pin "2") (pinfunction "2_2") (pintype "passive"))
      (node (ref "IC61") (pin "14") (pinfunction "SW_14") (pintype "passive"))
      (node (ref "IC61") (pin "26") (pinfunction "SW_26") (pintype "passive"))
      (node (ref "IC61") (pin "5") (pinfunction "SW_5") (pintype "passive"))
      (node (ref "IC61") (pin "6") (pinfunction "SW_6") (pintype "passive"))
      (node (ref "IC61") (pin "7") (pinfunction "SW_7") (pintype "passive"))
      (node (ref "L3") (pin "1") (pinfunction "1_1") (pintype "passive"))
    )
    (net (code "8") (name "Net-(C894-Pad2)") (class "Default")
      (node (ref "C894") (pin "2") (pinfunction "2_2") (pintype "passive"))
      (node (ref "IC62") (pin "14") (pinfunction "SW_14") (pintype "passive"))
      (node (ref "IC62") (pin "26") (pinfunction "SW_26") (pintype "passive"))
      (node (ref "IC62") (pin "5") (pinfunction "SW_5") (pintype "passive"))
      (node (ref "IC62") (pin "6") (pinfunction "SW_6") (pintype "passive"))
      (node (ref "IC62") (pin "7") (pinfunction "SW_7") (pintype "passive"))
      (node (ref "L4") (pin "1") (pinfunction "1_1") (pintype "passive"))
    )
    (net (code "9") (name "Net-(C896-Pad1)") (class "Default")
      (node (ref "C896") (pin "1") (pinfunction "1_1") (pintype "passive"))
      (node (ref "R433") (pin "1") (pinfunction "1_1") (pintype "passive"))
    )
    (net (code "10") (name "Net-(C898-Pad1)") (class "Default")
      (node (ref "C898") (pin "1") (pinfunction "1_1") (pintype "passive"))
      (node (ref "R434") (pin "1") (pinfunction "1_1") (pintype "passive"))
    )
    (net (code "11") (name "Net-(C906-Pad2)") (class "Default")
      (node (ref "C906") (pin "2") (pinfunction "2_2") (pintype "passive"))
      (node (ref "IC63") (pin "14") (pinfunction "SW_14") (pintype "passive"))
      (node (ref "IC63") (pin "26") (pinfunction "SW_26") (pintype "passive"))
      (node (ref "IC63") (pin "5") (pinfunction "SW_5") (pintype "passive"))
      (node (ref "IC63") (pin "6") (pinfunction "SW_6") (pintype "passive"))
      (node (ref "IC63") (pin "7") (pinfunction "SW_7") (pintype "passive"))
      (node (ref "L5") (pin "1") (pinfunction "1_1") (pintype "passive"))
    )
    (net (code "12") (name "Net-(C907-Pad2)") (class "Default")
      (node (ref "C907") (pin "2") (pinfunction "2_2") (pintype "passive"))
      (node (ref "IC64") (pin "14") (pinfunction "SW_14") (pintype "passive"))
      (node (ref "IC64") (pin "26") (pinfunction "SW_26") (pintype "passive"))
      (node (ref "IC64") (pin "5") (pinfunction "SW_5") (pintype "passive"))
      (node (ref "IC64") (pin "6") (pinfunction "SW_6") (pintype "passive"))
      (node (ref "IC64") (pin "7") (pinfunction "SW_7") (pintype "passive"))
      (node (ref "L6") (pin "1") (pinfunction "1_1") (pintype "passive"))
    )
    (net (code "13") (name "Net-(C909-Pad1)") (class "Default")
      (node (ref "C909") (pin "1") (pinfunction "1_1") (pintype "passive"))
      (node (ref "R442") (pin "1") (pinfunction "1_1") (pintype "passive"))
    )
    (net (code "14") (name "Net-(C922-Pad1)") (class "Default")
      (node (ref "C922") (pin "1") (pinfunction "1_1") (pintype "passive"))
      (node (ref "R451") (pin "1") (pinfunction "1_1") (pintype "passive"))
    )
    (net (code "15") (name "Net-(C924-Pad1)") (class "Default")
      (node (ref "C924") (pin "1") (pinfunction "1_1") (pintype "passive"))
      (node (ref "R452") (pin "1") (pinfunction "1_1") (pintype "passive"))
    )
    (net (code "16") (name "Net-(IC58-GATE)") (class "Default")
      (node (ref "IC58") (pin "3") (pinfunction "GATE_3") (pintype "passive"))
      (node (ref "VT20") (pin "4") (pinfunction "G_4") (pintype "passive"))
    )
    (net (code "17") (name "Net-(IC59-GATE)") (class "Default")
      (node (ref "IC59") (pin "3") (pinfunction "GATE_3") (pintype "passive"))
      (node (ref "VT19") (pin "4") (pinfunction "G_4") (pintype "passive"))
    )
    (net (code "18") (name "Net-(IC59-GND-Pad4)") (class "Default")
      (node (ref "IC59") (pin "4") (pinfunction "GND_4") (pintype "passive"))
      (node (ref "IC59") (pin "7") (pinfunction "GND_7") (pintype "passive"))
      (node (ref "VD1") (pin "3") (pinfunction "3_3") (pintype "passive"))
    )
    (net (code "19") (name "Net-(IC60-BST)") (class "Default")
      (node (ref "C882") (pin "1") (pinfunction "1_1") (pintype "passive"))
      (node (ref "IC60") (pin "15") (pinfunction "BST_15") (pintype "passive"))
    )
    (net (code "20") (name "Net-(IC60-COMP)") (class "Default")
      (node (ref "C895") (pin "1") (pinfunction "1_1") (pintype "passive"))
      (node (ref "IC60") (pin "1") (pinfunction "COMP_1") (pintype "passive"))
      (node (ref "R433") (pin "2") (pinfunction "2_2") (pintype "passive"))
    )
    (net (code "21") (name "Net-(IC60-FB)") (class "Default")
      (node (ref "IC60") (pin "2") (pinfunction "FB_2") (pintype "passive"))
      (node (ref "R425") (pin "1") (pinfunction "1_1") (pintype "passive"))
      (node (ref "R431") (pin "1") (pinfunction "1_1") (pintype "passive"))
    )
    (net (code "22") (name "Net-(IC60-RT)") (class "Default")
      (node (ref "IC60") (pin "22") (pinfunction "RT_22") (pintype "passive"))
      (node (ref "R429") (pin "1") (pinfunction "1_1") (pintype "passive"))
    )
    (net (code "23") (name "Net-(IC60-SS)") (class "Default")
      (node (ref "C899") (pin "1") (pinfunction "1_1") (pintype "passive"))
      (node (ref "IC60") (pin "24") (pinfunction "SS_24") (pintype "passive"))
    )
    (net (code "24") (name "Net-(IC60-SYNC)") (class "Default")
      (node (ref "IC60") (pin "23") (pinfunction "SYNC_23") (pintype "passive"))
      (node (ref "R426") (pin "1") (pinfunction "1_1") (pintype "passive"))
    )
    (net (code "25") (name "Net-(IC60-VREG)") (class "Default")
      (node (ref "C892") (pin "1") (pinfunction "1_1") (pintype "passive"))
      (node (ref "IC60") (pin "3") (pinfunction "VREG_3") (pintype "passive"))
    )
    (net (code "26") (name "Net-(IC61-BST)") (class "Default")
      (node (ref "C883") (pin "1") (pinfunction "1_1") (pintype "passive"))
      (node (ref "IC61") (pin "15") (pinfunction "BST_15") (pintype "passive"))
    )
    (net (code "27") (name "Net-(IC61-COMP)") (class "Default")
      (node (ref "C897") (pin "1") (pinfunction "1_1") (pintype "passive"))
      (node (ref "IC61") (pin "1") (pinfunction "COMP_1") (pintype "passive"))
      (node (ref "R434") (pin "2") (pinfunction "2_2") (pintype "passive"))
    )
    (net (code "28") (name "Net-(IC61-FB)") (class "Default")
      (node (ref "IC61") (pin "2") (pinfunction "FB_2") (pintype "passive"))
      (node (ref "R427") (pin "1") (pinfunction "1_1") (pintype "passive"))
      (node (ref "R432") (pin "1") (pinfunction "1_1") (pintype "passive"))
    )
    (net (code "29") (name "Net-(IC61-RT)") (class "Default")
      (node (ref "IC61") (pin "22") (pinfunction "RT_22") (pintype "passive"))
      (node (ref "R430") (pin "1") (pinfunction "1_1") (pintype "passive"))
    )
    (net (code "30") (name "Net-(IC61-SS)") (class "Default")
      (node (ref "C901") (pin "1") (pinfunction "1_1") (pintype "passive"))
      (node (ref "IC61") (pin "24") (pinfunction "SS_24") (pintype "passive"))
    )
    (net (code "31") (name "Net-(IC61-SYNC)") (class "Default")
      (node (ref "IC61") (pin "23") (pinfunction "SYNC_23") (pintype "passive"))
      (node (ref "R428") (pin "1") (pinfunction "1_1") (pintype "passive"))
    )
    (net (code "32") (name "Net-(IC61-VREG)") (class "Default")
      (node (ref "C893") (pin "1") (pinfunction "1_1") (pintype "passive"))
      (node (ref "IC61") (pin "3") (pinfunction "VREG_3") (pintype "passive"))
    )
    (net (code "33") (name "Net-(IC62-BST)") (class "Default")
      (node (ref "C894") (pin "1") (pinfunction "1_1") (pintype "passive"))
      (node (ref "IC62") (pin "15") (pinfunction "BST_15") (pintype "passive"))
    )
    (net (code "34") (name "Net-(IC62-COMP)") (class "Default")
      (node (ref "C908") (pin "1") (pinfunction "1_1") (pintype "passive"))
      (node (ref "IC62") (pin "1") (pinfunction "COMP_1") (pintype "passive"))
      (node (ref "R442") (pin "2") (pinfunction "2_2") (pintype "passive"))
    )
    (net (code "35") (name "Net-(IC62-FB)") (class "Default")
      (node (ref "IC62") (pin "2") (pinfunction "FB_2") (pintype "passive"))
      (node (ref "R436") (pin "1") (pinfunction "1_1") (pintype "passive"))
      (node (ref "R440") (pin "2") (pinfunction "2_2") (pintype "passive"))
    )
    (net (code "36") (name "Net-(IC62-RT)") (class "Default")
      (node (ref "IC62") (pin "22") (pinfunction "RT_22") (pintype "passive"))
      (node (ref "R439") (pin "1") (pinfunction "1_1") (pintype "passive"))
    )
    (net (code "37") (name "Net-(IC62-SS)") (class "Default")
      (node (ref "C911") (pin "1") (pinfunction "1_1") (pintype "passive"))
      (node (ref "IC62") (pin "24") (pinfunction "SS_24") (pintype "passive"))
    )
    (net (code "38") (name "Net-(IC62-SYNC)") (class "Default")
      (node (ref "IC62") (pin "23") (pinfunction "SYNC_23") (pintype "passive"))
      (node (ref "R437") (pin "1") (pinfunction "1_1") (pintype "passive"))
    )
    (net (code "39") (name "Net-(IC62-VREG)") (class "Default")
      (node (ref "C905") (pin "1") (pinfunction "1_1") (pintype "passive"))
      (node (ref "IC62") (pin "3") (pinfunction "VREG_3") (pintype "passive"))
    )
    (net (code "40") (name "Net-(IC63-BST)") (class "Default")
      (node (ref "C906") (pin "1") (pinfunction "1_1") (pintype "passive"))
      (node (ref "IC63") (pin "15") (pinfunction "BST_15") (pintype "passive"))
    )
    (net (code "41") (name "Net-(IC63-COMP)") (class "Default")
      (node (ref "C921") (pin "1") (pinfunction "1_1") (pintype "passive"))
      (node (ref "IC63") (pin "1") (pinfunction "COMP_1") (pintype "passive"))
      (node (ref "R451") (pin "2") (pinfunction "2_2") (pintype "passive"))
    )
    (net (code "42") (name "Net-(IC63-FB)") (class "Default")
      (node (ref "IC63") (pin "2") (pinfunction "FB_2") (pintype "passive"))
      (node (ref "R443") (pin "2") (pinfunction "2_2") (pintype "passive"))
      (node (ref "R449") (pin "2") (pinfunction "2_2") (pintype "passive"))
    )
    (net (code "43") (name "Net-(IC63-RT)") (class "Default")
      (node (ref "IC63") (pin "22") (pinfunction "RT_22") (pintype "passive"))
      (node (ref "R447") (pin "1") (pinfunction "1_1") (pintype "passive"))
    )
    (net (code "44") (name "Net-(IC63-SS)") (class "Default")
      (node (ref "C925") (pin "1") (pinfunction "1_1") (pintype "passive"))
      (node (ref "IC63") (pin "24") (pinfunction "SS_24") (pintype "passive"))
    )
    (net (code "45") (name "Net-(IC63-SYNC)") (class "Default")
      (node (ref "IC63") (pin "23") (pinfunction "SYNC_23") (pintype "passive"))
      (node (ref "R444") (pin "1") (pinfunction "1_1") (pintype "passive"))
    )
    (net (code "46") (name "Net-(IC63-VREG)") (class "Default")
      (node (ref "C919") (pin "1") (pinfunction "1_1") (pintype "passive"))
      (node (ref "IC63") (pin "3") (pinfunction "VREG_3") (pintype "passive"))
    )
    (net (code "47") (name "Net-(IC64-BST)") (class "Default")
      (node (ref "C907") (pin "1") (pinfunction "1_1") (pintype "passive"))
      (node (ref "IC64") (pin "15") (pinfunction "BST_15") (pintype "passive"))
    )
    (net (code "48") (name "Net-(IC64-COMP)") (class "Default")
      (node (ref "C923") (pin "1") (pinfunction "1_1") (pintype "passive"))
      (node (ref "IC64") (pin "1") (pinfunction "COMP_1") (pintype "passive"))
      (node (ref "R452") (pin "2") (pinfunction "2_2") (pintype "passive"))
    )
    (net (code "49") (name "Net-(IC64-FB)") (class "Default")
      (node (ref "IC64") (pin "2") (pinfunction "FB_2") (pintype "passive"))
      (node (ref "R445") (pin "1") (pinfunction "1_1") (pintype "passive"))
      (node (ref "R450") (pin "2") (pinfunction "2_2") (pintype "passive"))
    )
    (net (code "50") (name "Net-(IC64-RT)") (class "Default")
      (node (ref "IC64") (pin "22") (pinfunction "RT_22") (pintype "passive"))
      (node (ref "R448") (pin "1") (pinfunction "1_1") (pintype "passive"))
    )
    (net (code "51") (name "Net-(IC64-SS)") (class "Default")
      (node (ref "C926") (pin "2") (pinfunction "2_2") (pintype "passive"))
      (node (ref "IC64") (pin "24") (pinfunction "SS_24") (pintype "passive"))
    )
    (net (code "52") (name "Net-(IC64-SYNC)") (class "Default")
      (node (ref "IC64") (pin "23") (pinfunction "SYNC_23") (pintype "passive"))
      (node (ref "R446") (pin "1") (pinfunction "1_1") (pintype "passive"))
    )
    (net (code "53") (name "Net-(IC64-VREG)") (class "Default")
      (node (ref "C920") (pin "1") (pinfunction "1_1") (pintype "passive"))
      (node (ref "IC64") (pin "3") (pinfunction "VREG_3") (pintype "passive"))
    )
    (net (code "54") (name "Net-(LED7-PadA)") (class "Default")
      (node (ref "LED7") (pin "A") (pinfunction "A_A") (pintype "power_in"))
      (node (ref "R453") (pin "1") (pinfunction "1_1") (pintype "passive"))
    )
    (net (code "55") (name "VCC1P1") (class "Default")
      (node (ref "C889") (pin "2") (pinfunction "2_2") (pintype "passive"))
      (node (ref "C890") (pin "2") (pinfunction "2_2") (pintype "passive"))
      (node (ref "C891") (pin "2") (pinfunction "2_2") (pintype "passive"))
      (node (ref "L3") (pin "2") (pinfunction "2_2") (pintype "passive"))
      (node (ref "R427") (pin "2") (pinfunction "2_2") (pintype "passive"))
    )
    (net (code "56") (name "VCC1P5") (class "Default")
      (node (ref "C886") (pin "2") (pinfunction "2_2") (pintype "passive"))
      (node (ref "C887") (pin "2") (pinfunction "2_2") (pintype "passive"))
      (node (ref "C888") (pin "2") (pinfunction "2_2") (pintype "passive"))
      (node (ref "L2") (pin "2") (pinfunction "2_2") (pintype "passive"))
      (node (ref "R425") (pin "2") (pinfunction "2_2") (pintype "passive"))
    )
    (net (code "57") (name "VCC2P5") (class "Default")
      (node (ref "C902") (pin "2") (pinfunction "2_2") (pintype "passive"))
      (node (ref "C903") (pin "2") (pinfunction "2_2") (pintype "passive"))
      (node (ref "C904") (pin "2") (pinfunction "2_2") (pintype "passive"))
      (node (ref "L4") (pin "2") (pinfunction "2_2") (pintype "passive"))
      (node (ref "R421") (pin "2") (pinfunction "2_2") (pintype "passive"))
      (node (ref "R422") (pin "2") (pinfunction "2_2") (pintype "passive"))
      (node (ref "R436") (pin "2") (pinfunction "2_2") (pintype "passive"))
    )
    (net (code "58") (name "VCC3P3") (class "Default")
      (node (ref "C913") (pin "2") (pinfunction "2_2") (pintype "passive"))
      (node (ref "C914") (pin "2") (pinfunction "2_2") (pintype "passive"))
      (node (ref "C915") (pin "2") (pinfunction "2_2") (pintype "passive"))
      (node (ref "L5") (pin "2") (pinfunction "2_2") (pintype "passive"))
      (node (ref "R419") (pin "2") (pinfunction "2_2") (pintype "passive"))
      (node (ref "R420") (pin "2") (pinfunction "2_2") (pintype "passive"))
      (node (ref "R443") (pin "1") (pinfunction "1_1") (pintype "passive"))
      (node (ref "R453") (pin "2") (pinfunction "2_2") (pintype "passive"))
    )
    (net (code "59") (name "VCC5P0") (class "Default")
      (node (ref "C916") (pin "2") (pinfunction "2_2") (pintype "passive"))
      (node (ref "C917") (pin "2") (pinfunction "2_2") (pintype "passive"))
      (node (ref "C918") (pin "2") (pinfunction "2_2") (pintype "passive"))
      (node (ref "L6") (pin "2") (pinfunction "2_2") (pintype "passive"))
      (node (ref "R445") (pin "2") (pinfunction "2_2") (pintype "passive"))
    )
    (net (code "60") (name "VCC12P0") (class "Default")
      (node (ref "C867") (pin "2") (pinfunction "2_2") (pintype "passive"))
      (node (ref "C868") (pin "2") (pinfunction "2_2") (pintype "passive"))
      (node (ref "C869") (pin "2") (pinfunction "2_2") (pintype "passive"))
      (node (ref "C870") (pin "2") (pinfunction "2_2") (pintype "passive"))
      (node (ref "C871") (pin "2") (pinfunction "2_2") (pintype "passive"))
      (node (ref "C872") (pin "1") (pinfunction "1_1") (pintype "passive"))
      (node (ref "C876") (pin "1") (pinfunction "1_1") (pintype "passive"))
      (node (ref "C884") (pin "2") (pinfunction "2_2") (pintype "passive"))
      (node (ref "C885") (pin "2") (pinfunction "2_2") (pintype "passive"))
      (node (ref "C900") (pin "2") (pinfunction "2_2") (pintype "passive"))
      (node (ref "C910") (pin "2") (pinfunction "2_2") (pintype "passive"))
      (node (ref "C912") (pin "2") (pinfunction "2_2") (pintype "passive"))
      (node (ref "IC58") (pin "1") (pinfunction "OUT_1") (pintype "passive"))
      (node (ref "IC58") (pin "6") (pinfunction "VDD_6") (pintype "passive"))
      (node (ref "IC59") (pin "1") (pinfunction "OUT_1") (pintype "passive"))
      (node (ref "IC59") (pin "6") (pinfunction "VDD_6") (pintype "passive"))
      (node (ref "IC60") (pin "16") (pinfunction "PVIN_16") (pintype "passive"))
      (node (ref "IC60") (pin "17") (pinfunction "PVIN_17") (pintype "passive"))
      (node (ref "IC60") (pin "18") (pinfunction "PVIN_18") (pintype "passive"))
      (node (ref "IC60") (pin "19") (pinfunction "PVIN_19") (pintype "passive"))
      (node (ref "IC61") (pin "16") (pinfunction "PVIN_16") (pintype "passive"))
      (node (ref "IC61") (pin "17") (pinfunction "PVIN_17") (pintype "passive"))
      (node (ref "IC61") (pin "18") (pinfunction "PVIN_18") (pintype "passive"))
      (node (ref "IC61") (pin "19") (pinfunction "PVIN_19") (pintype "passive"))
      (node (ref "IC62") (pin "16") (pinfunction "PVIN_16") (pintype "passive"))
      (node (ref "IC62") (pin "17") (pinfunction "PVIN_17") (pintype "passive"))
      (node (ref "IC62") (pin "18") (pinfunction "PVIN_18") (pintype "passive"))
      (node (ref "IC62") (pin "19") (pinfunction "PVIN_19") (pintype "passive"))
      (node (ref "IC63") (pin "16") (pinfunction "PVIN_16") (pintype "passive"))
      (node (ref "IC63") (pin "17") (pinfunction "PVIN_17") (pintype "passive"))
      (node (ref "IC63") (pin "18") (pinfunction "PVIN_18") (pintype "passive"))
      (node (ref "IC63") (pin "19") (pinfunction "PVIN_19") (pintype "passive"))
      (node (ref "IC64") (pin "16") (pinfunction "PVIN_16") (pintype "passive"))
      (node (ref "IC64") (pin "17") (pinfunction "PVIN_17") (pintype "passive"))
      (node (ref "IC64") (pin "18") (pinfunction "PVIN_18") (pintype "passive"))
      (node (ref "IC64") (pin "19") (pinfunction "PVIN_19") (pintype "passive"))
      (node (ref "J39") (pin "2") (pinfunction "2_2") (pintype "passive"))
      (node (ref "R417") (pin "1") (pinfunction "1_1") (pintype "passive"))
      (node (ref "R418") (pin "1") (pinfunction "1_1") (pintype "passive"))
      (node (ref "R423") (pin "1") (pinfunction "1_1") (pintype "passive"))
      (node (ref "R424") (pin "2") (pinfunction "2_2") (pintype "passive"))
      (node (ref "R435") (pin "1") (pinfunction "1_1") (pintype "passive"))
      (node (ref "SW3") (pin "1") (pinfunction "1_1") (pintype "passive"))
      (node (ref "VT19") (pin "5") (pinfunction "D_5") (pintype "passive"))
      (node (ref "VT19") (pin "6") (pinfunction "D_6") (pintype "passive"))
      (node (ref "VT19") (pin "7") (pinfunction "D_7") (pintype "passive"))
      (node (ref "VT19") (pin "8") (pinfunction "D_8") (pintype "passive"))
      (node (ref "VT20") (pin "5") (pinfunction "D_5") (pintype "passive"))
      (node (ref "VT20") (pin "6") (pinfunction "D_6") (pintype "passive"))
      (node (ref "VT20") (pin "7") (pinfunction "D_7") (pintype "passive"))
      (node (ref "VT20") (pin "8") (pinfunction "D_8") (pintype "passive"))
    )
    (net (code "61") (name "VCC12P0_PCIE") (class "Default")
      (node (ref "IC58") (pin "2") (pinfunction "IN_2") (pintype "passive"))
      (node (ref "R418") (pin "2") (pinfunction "2_2") (pintype "passive"))
      (node (ref "VT20") (pin "1") (pinfunction "S_1") (pintype "passive"))
      (node (ref "VT20") (pin "2") (pinfunction "S_2") (pintype "passive"))
      (node (ref "VT20") (pin "3") (pinfunction "S_3") (pintype "passive"))
    )
    (net (code "62") (name "VDIO_DAC_FPGA") (class "Default")
      (node (ref "R420") (pin "1") (pinfunction "1_1") (pintype "passive"))
      (node (ref "R422") (pin "1") (pinfunction "1_1") (pintype "passive"))
    )
    (net (code "63") (name "VDIO_LMS1") (class "Default")
      (node (ref "C874") (pin "2") (pinfunction "2_2") (pintype "passive"))
      (node (ref "C875") (pin "1") (pinfunction "1_1") (pintype "passive"))
      (node (ref "FR110") (pin "2") (pinfunction "2_2") (pintype "passive"))
    )
    (net (code "64") (name "VDIO_LMS2") (class "Default")
      (node (ref "C880") (pin "2") (pinfunction "2_2") (pintype "passive"))
      (node (ref "C881") (pin "1") (pinfunction "1_1") (pintype "passive"))
      (node (ref "FR111") (pin "2") (pinfunction "2_2") (pintype "passive"))
    )
    (net (code "65") (name "VDIO_LMS_FPGA") (class "Default")
      (node (ref "FR110") (pin "1") (pinfunction "1_1") (pintype "passive"))
      (node (ref "FR111") (pin "1") (pinfunction "1_1") (pintype "passive"))
      (node (ref "R419") (pin "1") (pinfunction "1_1") (pintype "passive"))
      (node (ref "R421") (pin "1") (pinfunction "1_1") (pintype "passive"))
    )
    (net (code "66") (name "unconnected-(IC58-NC-Pad5)") (class "Default")
      (node (ref "IC58") (pin "5") (pinfunction "NC_5") (pintype "passive+no_connect"))
    )
    (net (code "67") (name "unconnected-(IC59-NC-Pad5)") (class "Default")
      (node (ref "IC59") (pin "5") (pinfunction "NC_5") (pintype "passive+no_connect"))
    )
    (net (code "68") (name "unconnected-(IC60-PGOOD-Pad21)") (class "Default")
      (node (ref "IC60") (pin "21") (pinfunction "PGOOD_21") (pintype "passive+no_connect"))
    )
    (net (code "69") (name "unconnected-(IC62-PGOOD-Pad21)") (class "Default")
      (node (ref "IC62") (pin "21") (pinfunction "PGOOD_21") (pintype "passive+no_connect"))
    )
    (net (code "70") (name "unconnected-(IC63-PGOOD-Pad21)") (class "Default")
      (node (ref "IC63") (pin "21") (pinfunction "PGOOD_21") (pintype "passive+no_connect"))
    )
    (net (code "71") (name "unconnected-(IC64-PGOOD-Pad21)") (class "Default")
      (node (ref "IC64") (pin "21") (pinfunction "PGOOD_21") (pintype "passive+no_connect"))
    )
    (net (code "72") (name "unconnected-(SW3-Pad3)") (class "Default")
      (node (ref "SW3") (pin "3") (pinfunction "3_3") (pintype "passive+no_connect"))
    )
  )
)
